# Schematic1.net
KiCad netlist of a schematic drawn in EAGLE
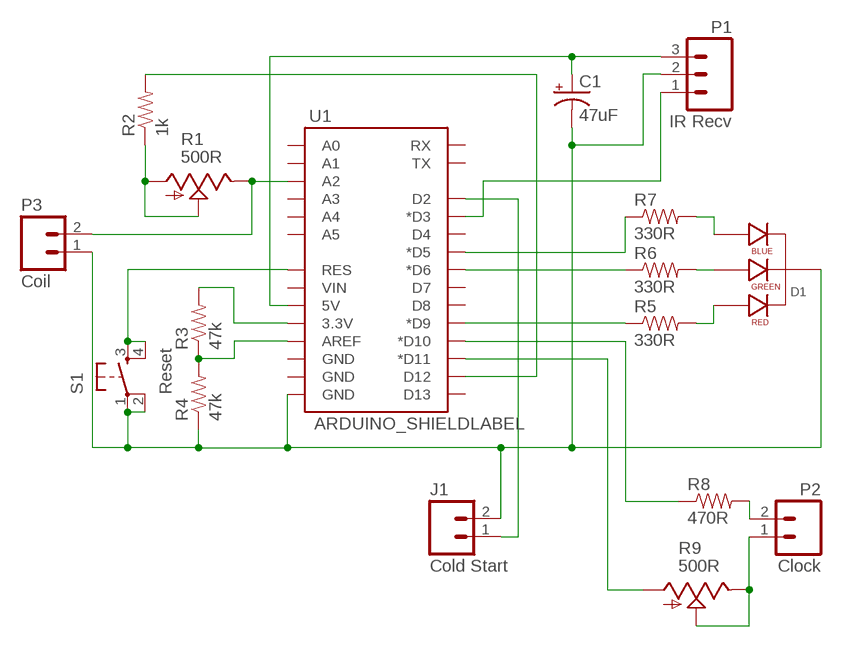
[diagram p0: schematic, sheet 1]

(export (version "E")
  (design (tool "Eeschema 10.0.6"))
  (components
    (comp (ref "C1")
      (value "47uF")
      (footprint "eagle-import:CPOL-RADIAL-10UF-25V")
      (libsource (lib "eagle-import") (part "CAP_POLPTH2"))
    )
    (comp (ref "D1")
      (value "LED-RGB-CC-THRUDIFFUSE")
      (footprint "eagle-import:LED-RGB-THRU")
      (libsource (lib "eagle-import") (part "LED-RGB-CC-THRUDIFFUSE"))
    )
    (comp (ref "J1")
      (value "Cold Start")
      (footprint "eagle-import:1X02")
      (libsource (lib "eagle-import") (part "M02PTH"))
    )
    (comp (ref "P1")
      (value "IR Recv")
      (footprint "eagle-import:1X03")
      (libsource (lib "eagle-import") (part "M03PTH"))
    )
    (comp (ref "P2")
      (value "Clock")
      (footprint "eagle-import:1X02")
      (libsource (lib "eagle-import") (part "M02PTH"))
    )
    (comp (ref "P3")
      (value "Coil")
      (footprint "eagle-import:1X02")
      (libsource (lib "eagle-import") (part "M02PTH"))
    )
    (comp (ref "R1")
      (value "500R")
      (footprint "eagle-import:ECP10P")
      (libsource (lib "eagle-import") (part "TRIM_US-ECP10P"))
    )
    (comp (ref "R2")
      (value "1k")
      (footprint "eagle-import:AXIAL-0.3-KIT")
      (libsource (lib "eagle-import") (part "10KOHM1/6W5%(PTH)KIT"))
    )
    (comp (ref "R3")
      (value "47k")
      (footprint "eagle-import:AXIAL-0.3-KIT")
      (libsource (lib "eagle-import") (part "10KOHM1/6W5%(PTH)KIT"))
    )
    (comp (ref "R4")
      (value "47k")
      (footprint "eagle-import:AXIAL-0.3-KIT")
      (libsource (lib "eagle-import") (part "10KOHM1/6W5%(PTH)KIT"))
    )
    (comp (ref "R5")
      (value "330R")
      (footprint "eagle-import:AXIAL-0.3-KIT")
      (libsource (lib "eagle-import") (part "10KOHM1/6W5%(PTH)KIT"))
    )
    (comp (ref "R6")
      (value "330R")
      (footprint "eagle-import:AXIAL-0.3-KIT")
      (libsource (lib "eagle-import") (part "10KOHM1/6W5%(PTH)KIT"))
    )
    (comp (ref "R7")
      (value "330R")
      (footprint "eagle-import:AXIAL-0.3-KIT")
      (libsource (lib "eagle-import") (part "10KOHM1/6W5%(PTH)KIT"))
    )
    (comp (ref "R8")
      (value "470R")
      (footprint "eagle-import:AXIAL-0.3-KIT")
      (libsource (lib "eagle-import") (part "10KOHM1/6W5%(PTH)KIT"))
    )
    (comp (ref "R9")
      (value "500R")
      (footprint "eagle-import:ECP10P")
      (libsource (lib "eagle-import") (part "TRIM_US-ECP10P"))
    )
    (comp (ref "S1")
      (value "Reset")
      (footprint "eagle-import:TACTILE-PTH")
      (libsource (lib "eagle-import") (part "TAC_SWITCHPTH"))
    )
    (comp (ref "U1")
      (value "ARDUINO_SHIELDLABEL")
      (footprint "eagle-import:DUEMILANOVE_SHIELD")
      (libsource (lib "eagle-import") (part "ARDUINO_SHIELDLABEL"))
    )
  )
  (nets
    (net (code "1") (name "Net-(C1-+)") (class "Default")
      (node (ref "C1") (pin "1") (pinfunction "+_1") (pintype "passive"))
      (node (ref "P1") (pin "3") (pinfunction "3_3") (pintype "passive"))
      (node (ref "U1") (pin "5V") (pinfunction "5V_5V") (pintype "bidirectional"))
    )
    (net (code "2") (name "Net-(C1--)") (class "Default")
      (node (ref "C1") (pin "2") (pinfunction "-_2") (pintype "passive"))
      (node (ref "D1") (pin "2") (pinfunction "CATHODE_2") (pintype "bidirectional"))
      (node (ref "J1") (pin "2") (pinfunction "2_2") (pintype "passive"))
      (node (ref "P1") (pin "2") (pinfunction "2_2") (pintype "passive"))
      (node (ref "P3") (pin "1") (pinfunction "1_1") (pintype "passive"))
      (node (ref "R4") (pin "P$1") (pinfunction "1_P$1") (pintype "passive"))
      (node (ref "S1") (pin "1") (pinfunction "1_1") (pintype "passive"))
      (node (ref "S1") (pin "2") (pinfunction "2_2") (pintype "passive"))
      (node (ref "U1") (pin "GND@0") (pinfunction "GND_GND@0") (pintype "bidirectional"))
    )
    (net (code "3") (name "Net-(D1-BLUE_ANODE)") (class "Default")
      (node (ref "D1") (pin "4") (pinfunction "BLUE_ANODE_4") (pintype "bidirectional"))
      (node (ref "R7") (pin "P$2") (pinfunction "2_P$2") (pintype "passive"))
    )
    (net (code "4") (name "Net-(D1-GREEN_ANODE)") (class "Default")
      (node (ref "D1") (pin "3") (pinfunction "GREEN_ANODE_3") (pintype "bidirectional"))
      (node (ref "R6") (pin "P$2") (pinfunction "2_P$2") (pintype "passive"))
    )
    (net (code "5") (name "Net-(D1-RED_ANODE)") (class "Default")
      (node (ref "D1") (pin "1") (pinfunction "RED_ANODE_1") (pintype "bidirectional"))
      (node (ref "R5") (pin "P$2") (pinfunction "2_P$2") (pintype "passive"))
    )
    (net (code "6") (name "Net-(J1-Pad1)") (class "Default")
      (node (ref "J1") (pin "1") (pinfunction "1_1") (pintype "passive"))
      (node (ref "U1") (pin "D2") (pinfunction "D2_D2") (pintype "bidirectional"))
    )
    (net (code "7") (name "Net-(P2-Pad1)") (class "Default")
      (node (ref "P2") (pin "1") (pinfunction "1_1") (pintype "passive"))
      (node (ref "R9") (pin "E") (pinfunction "E_E") (pintype "passive"))
      (node (ref "R9") (pin "S") (pinfunction "S_S") (pintype "passive"))
    )
    (net (code "8") (name "Net-(P3-Pad2)") (class "Default")
      (node (ref "P3") (pin "2") (pinfunction "2_2") (pintype "passive"))
      (node (ref "R1") (pin "E") (pinfunction "E_E") (pintype "passive"))
      (node (ref "U1") (pin "A2") (pinfunction "A2_A2") (pintype "bidirectional"))
    )
    (net (code "9") (name "Net-(R2-1)") (class "Default")
      (node (ref "R1") (pin "A") (pinfunction "A_A") (pintype "passive"))
      (node (ref "R1") (pin "S") (pinfunction "S_S") (pintype "passive"))
      (node (ref "R2") (pin "P$1") (pinfunction "1_P$1") (pintype "passive"))
    )
    (net (code "10") (name "Net-(R2-2)") (class "Default")
      (node (ref "R2") (pin "P$2") (pinfunction "2_P$2") (pintype "passive"))
      (node (ref "U1") (pin "D12") (pinfunction "D12_D12") (pintype "bidirectional"))
    )
    (net (code "11") (name "Net-(R3-1)") (class "Default")
      (node (ref "R3") (pin "P$1") (pinfunction "1_P$1") (pintype "passive"))
      (node (ref "R4") (pin "P$2") (pinfunction "2_P$2") (pintype "passive"))
      (node (ref "U1") (pin "AREF") (pinfunction "AREF_AREF") (pintype "bidirectional"))
    )
    (net (code "12") (name "Net-(R3-2)") (class "Default")
      (node (ref "R3") (pin "P$2") (pinfunction "2_P$2") (pintype "passive"))
      (node (ref "U1") (pin "3.3V") (pinfunction "3.3V_3.3V") (pintype "bidirectional"))
    )
    (net (code "13") (name "Net-(R5-1)") (class "Default")
      (node (ref "R5") (pin "P$1") (pinfunction "1_P$1") (pintype "passive"))
      (node (ref "U1") (pin "D9") (pinfunction "*D9_D9") (pintype "bidirectional"))
    )
    (net (code "14") (name "Net-(R6-1)") (class "Default")
      (node (ref "R6") (pin "P$1") (pinfunction "1_P$1") (pintype "passive"))
      (node (ref "U1") (pin "D6") (pinfunction "*D6_D6") (pintype "bidirectional"))
    )
    (net (code "15") (name "Net-(R7-1)") (class "Default")
      (node (ref "R7") (pin "P$1") (pinfunction "1_P$1") (pintype "passive"))
      (node (ref "U1") (pin "D5") (pinfunction "*D5_D5") (pintype "bidirectional"))
    )
    (net (code "16") (name "Net-(R8-1)") (class "Default")
      (node (ref "R8") (pin "P$1") (pinfunction "1_P$1") (pintype "passive"))
      (node (ref "U1") (pin "D10") (pinfunction "*D10_D10") (pintype "bidirectional"))
    )
    (net (code "17") (name "Net-(R8-2)") (class "Default")
      (node (ref "P2") (pin "2") (pinfunction "2_2") (pintype "passive"))
      (node (ref "R8") (pin "P$2") (pinfunction "2_P$2") (pintype "passive"))
    )
    (net (code "18") (name "Net-(S1-Pad3)") (class "Default")
      (node (ref "S1") (pin "3") (pinfunction "3_3") (pintype "passive"))
      (node (ref "S1") (pin "4") (pinfunction "4_4") (pintype "passive"))
      (node (ref "U1") (pin "RES") (pinfunction "RES_RES") (pintype "bidirectional"))
    )
    (net (code "19") (name "Net-(U1-*D3)") (class "Default")
      (node (ref "P1") (pin "1") (pinfunction "1_1") (pintype "passive"))
      (node (ref "U1") (pin "D3") (pinfunction "*D3_D3") (pintype "bidirectional"))
    )
    (net (code "20") (name "Net-(U1-*D11)") (class "Default")
      (node (ref "R9") (pin "A") (pinfunction "A_A") (pintype "passive"))
      (node (ref "U1") (pin "D11") (pinfunction "*D11_D11") (pintype "bidirectional"))
    )
    (net (code "21") (name "unconnected-(U1-GND-PadGND@1)") (class "Default")
      (node (ref "U1") (pin "GND@1") (pinfunction "GND_GND@1") (pintype "bidirectional"))
    )
    (net (code "22") (name "unconnected-(U1-GND-PadGND@2)") (class "Default")
      (node (ref "U1") (pin "GND@2") (pinfunction "GND_GND@2") (pintype "bidirectional"))
    )
    (net (code "23") (name "unconnected-(U1-PadA0)") (class "Default")
      (node (ref "U1") (pin "A0") (pinfunction "A0_A0") (pintype "bidirectional"))
    )
    (net (code "24") (name "unconnected-(U1-PadA1)") (class "Default")
      (node (ref "U1") (pin "A1") (pinfunction "A1_A1") (pintype "bidirectional"))
    )
    (net (code "25") (name "unconnected-(U1-PadA3)") (class "Default")
      (node (ref "U1") (pin "A3") (pinfunction "A3_A3") (pintype "bidirectional"))
    )
    (net (code "26") (name "unconnected-(U1-PadA4)") (class "Default")
      (node (ref "U1") (pin "A4") (pinfunction "A4_A4") (pintype "bidirectional"))
    )
    (net (code "27") (name "unconnected-(U1-PadA5)") (class "Default")
      (node (ref "U1") (pin "A5") (pinfunction "A5_A5") (pintype "bidirectional"))
    )
    (net (code "28") (name "unconnected-(U1-PadD4)") (class "Default")
      (node (ref "U1") (pin "D4") (pinfunction "D4_D4") (pintype "bidirectional"))
    )
    (net (code "29") (name "unconnected-(U1-PadD7)") (class "Default")
      (node (ref "U1") (pin "D7") (pinfunction "D7_D7") (pintype "bidirectional"))
    )
    (net (code "30") (name "unconnected-(U1-PadD8)") (class "Default")
      (node (ref "U1") (pin "D8") (pinfunction "D8_D8") (pintype "bidirectional"))
    )
    (net (code "31") (name "unconnected-(U1-PadD13)") (class "Default")
      (node (ref "U1") (pin "D13") (pinfunction "D13_D13") (pintype "bidirectional"))
    )
    (net (code "32") (name "unconnected-(U1-PadRX)") (class "Default")
      (node (ref "U1") (pin "RX") (pinfunction "RX_RX") (pintype "bidirectional"))
    )
    (net (code "33") (name "unconnected-(U1-PadTX)") (class "Default")
      (node (ref "U1") (pin "TX") (pinfunction "TX_TX") (pintype "bidirectional"))
    )
    (net (code "34") (name "unconnected-(U1-PadVIN)") (class "Default")
      (node (ref "U1") (pin "VIN") (pinfunction "VIN_VIN") (pintype "bidirectional"))
    )
  )
)
